# ULA.net
KiCad netlist of a schematic drawn in EAGLE
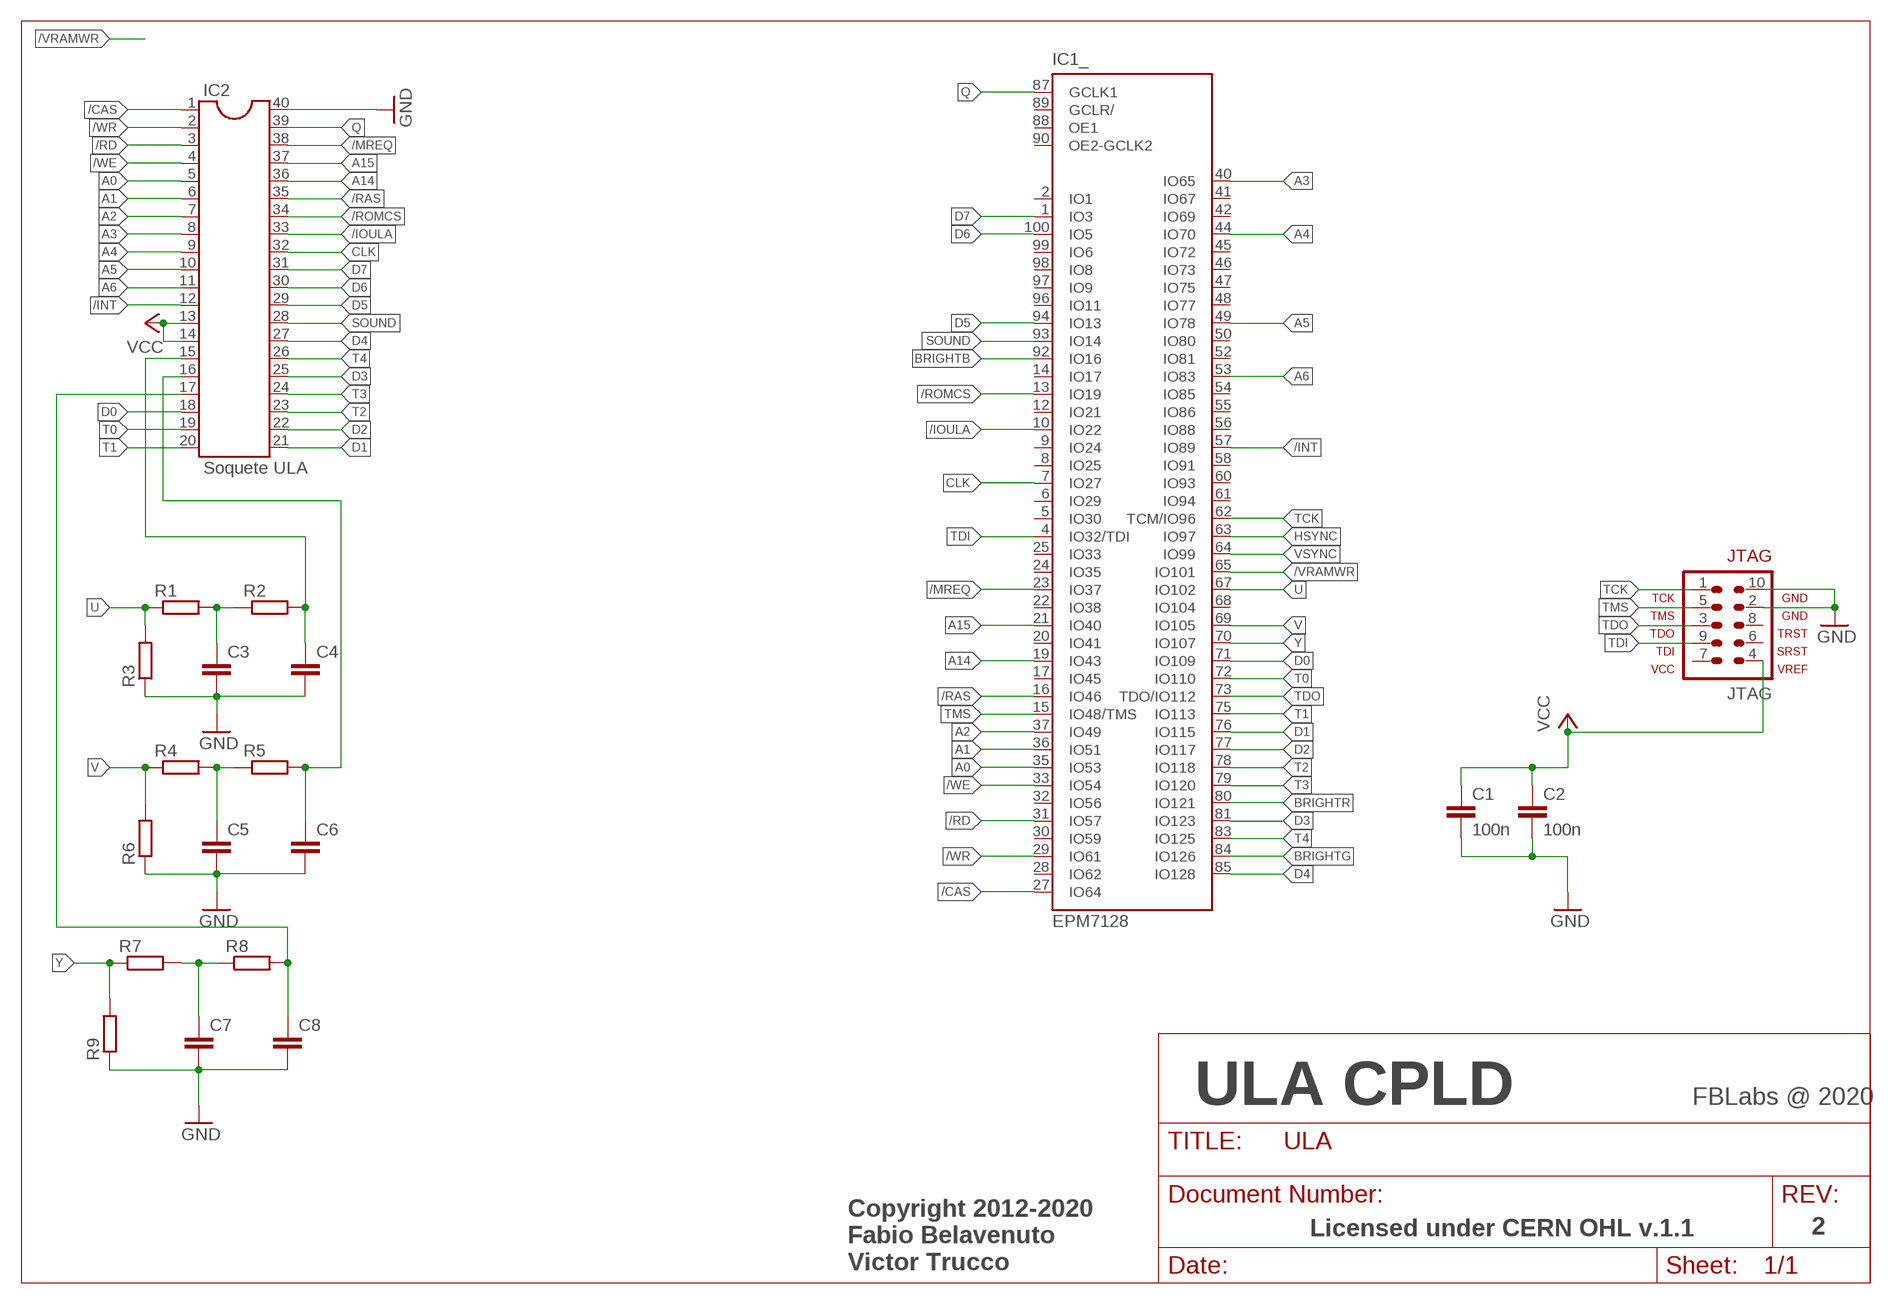
[diagram p0: schematic, sheet 1]

(export (version "E")
  (design (tool "Eeschema 10.0.6"))
  (components
    (comp (ref "C1")
      (value "100n")
      (footprint "eagle-import:C1206")
      (libsource (lib "eagle-import") (part "C-EUC1206"))
    )
    (comp (ref "C2")
      (value "100n")
      (footprint "eagle-import:C1206")
      (libsource (lib "eagle-import") (part "C-EUC1206"))
    )
    (comp (ref "C3")
      (value "C-EUC0805K")
      (footprint "eagle-import:C0805K")
      (libsource (lib "eagle-import") (part "rcl_334_C-EUC0805K"))
    )
    (comp (ref "C4")
      (value "C-EUC0805K")
      (footprint "eagle-import:C0805K")
      (libsource (lib "eagle-import") (part "rcl_334_C-EUC0805K"))
    )
    (comp (ref "C5")
      (value "C-EUC0805K")
      (footprint "eagle-import:C0805K")
      (libsource (lib "eagle-import") (part "rcl_334_C-EUC0805K"))
    )
    (comp (ref "C6")
      (value "C-EUC0805K")
      (footprint "eagle-import:C0805K")
      (libsource (lib "eagle-import") (part "rcl_334_C-EUC0805K"))
    )
    (comp (ref "C7")
      (value "C-EUC0805K")
      (footprint "eagle-import:C0805K")
      (libsource (lib "eagle-import") (part "rcl_334_C-EUC0805K"))
    )
    (comp (ref "C8")
      (value "C-EUC0805K")
      (footprint "eagle-import:C0805K")
      (libsource (lib "eagle-import") (part "rcl_334_C-EUC0805K"))
    )
    (comp (ref "IC1")
      (value "EPM7128")
      (footprint "eagle-import:TQFP100")
      (fields (field (name "MPN") "EPM7128STC100-7N"))
      (libsource (lib "eagle-import") (part "EPM7128-?100T"))
    )
    (comp (ref "IC2")
      (value "Soquete ULA")
      (footprint "eagle-import:DIL40")
      (libsource (lib "eagle-import") (part "DIL40"))
    )
    (comp (ref "JTAG")
      (value "AVR-JTAG-10")
      (footprint "eagle-import:AVR-JTAG-10")
      (libsource (lib "eagle-import") (part "AVR-JTAG-10"))
    )
    (comp (ref "R1")
      (value "R-EU_M0805")
      (footprint "eagle-import:M0805")
      (libsource (lib "eagle-import") (part "R-EU_M0805"))
    )
    (comp (ref "R2")
      (value "R-EU_M0805")
      (footprint "eagle-import:M0805")
      (libsource (lib "eagle-import") (part "R-EU_M0805"))
    )
    (comp (ref "R3")
      (value "R-EU_M0805")
      (footprint "eagle-import:M0805")
      (libsource (lib "eagle-import") (part "R-EU_M0805"))
    )
    (comp (ref "R4")
      (value "R-EU_M0805")
      (footprint "eagle-import:M0805")
      (libsource (lib "eagle-import") (part "R-EU_M0805"))
    )
    (comp (ref "R5")
      (value "R-EU_M0805")
      (footprint "eagle-import:M0805")
      (libsource (lib "eagle-import") (part "R-EU_M0805"))
    )
    (comp (ref "R6")
      (value "R-EU_M0805")
      (footprint "eagle-import:M0805")
      (libsource (lib "eagle-import") (part "R-EU_M0805"))
    )
    (comp (ref "R7")
      (value "R-EU_M0805")
      (footprint "eagle-import:M0805")
      (libsource (lib "eagle-import") (part "R-EU_M0805"))
    )
    (comp (ref "R8")
      (value "R-EU_M0805")
      (footprint "eagle-import:M0805")
      (libsource (lib "eagle-import") (part "R-EU_M0805"))
    )
    (comp (ref "R9")
      (value "R-EU_M0805")
      (footprint "eagle-import:M0805")
      (libsource (lib "eagle-import") (part "R-EU_M0805"))
    )
  )
  (nets
    (net (code "1") (name "A0") (class "Default")
      (node (ref "IC1") (pin "35") (pinfunction "IO53_35") (pintype "bidirectional"))
      (node (ref "IC2") (pin "5") (pinfunction "5_5") (pintype "passive"))
    )
    (net (code "2") (name "A1") (class "Default")
      (node (ref "IC1") (pin "36") (pinfunction "IO51_36") (pintype "bidirectional"))
      (node (ref "IC2") (pin "6") (pinfunction "6_6") (pintype "passive"))
    )
    (net (code "3") (name "A2") (class "Default")
      (node (ref "IC1") (pin "37") (pinfunction "IO49_37") (pintype "bidirectional"))
      (node (ref "IC2") (pin "7") (pinfunction "7_7") (pintype "passive"))
    )
    (net (code "4") (name "A3") (class "Default")
      (node (ref "IC1") (pin "40") (pinfunction "IO65_40") (pintype "bidirectional"))
      (node (ref "IC2") (pin "8") (pinfunction "8_8") (pintype "passive"))
    )
    (net (code "5") (name "A4") (class "Default")
      (node (ref "IC1") (pin "44") (pinfunction "IO70_44") (pintype "bidirectional"))
      (node (ref "IC2") (pin "9") (pinfunction "9_9") (pintype "passive"))
    )
    (net (code "6") (name "A5") (class "Default")
      (node (ref "IC1") (pin "49") (pinfunction "IO78_49") (pintype "bidirectional"))
      (node (ref "IC2") (pin "10") (pinfunction "10_10") (pintype "passive"))
    )
    (net (code "7") (name "A6") (class "Default")
      (node (ref "IC1") (pin "53") (pinfunction "IO83_53") (pintype "bidirectional"))
      (node (ref "IC2") (pin "11") (pinfunction "11_11") (pintype "passive"))
    )
    (net (code "8") (name "A14") (class "Default")
      (node (ref "IC1") (pin "19") (pinfunction "IO43_19") (pintype "bidirectional"))
      (node (ref "IC2") (pin "36") (pinfunction "36_36") (pintype "passive"))
    )
    (net (code "9") (name "A15") (class "Default")
      (node (ref "IC1") (pin "21") (pinfunction "IO40_21") (pintype "bidirectional"))
      (node (ref "IC2") (pin "37") (pinfunction "37_37") (pintype "passive"))
    )
    (net (code "10") (name "BRIGHTB") (class "Default")
      (node (ref "IC1") (pin "92") (pinfunction "IO16_92") (pintype "bidirectional"))
    )
    (net (code "11") (name "BRIGHTG") (class "Default")
      (node (ref "IC1") (pin "84") (pinfunction "IO126_84") (pintype "bidirectional"))
    )
    (net (code "12") (name "BRIGHTR") (class "Default")
      (node (ref "IC1") (pin "80") (pinfunction "IO121_80") (pintype "bidirectional"))
    )
    (net (code "13") (name "CLK") (class "Default")
      (node (ref "IC1") (pin "7") (pinfunction "IO27_7") (pintype "bidirectional"))
      (node (ref "IC2") (pin "32") (pinfunction "32_32") (pintype "passive"))
    )
    (net (code "14") (name "D0") (class "Default")
      (node (ref "IC1") (pin "71") (pinfunction "IO109_71") (pintype "bidirectional"))
      (node (ref "IC2") (pin "18") (pinfunction "18_18") (pintype "passive"))
    )
    (net (code "15") (name "D1") (class "Default")
      (node (ref "IC1") (pin "76") (pinfunction "IO115_76") (pintype "bidirectional"))
      (node (ref "IC2") (pin "21") (pinfunction "21_21") (pintype "passive"))
    )
    (net (code "16") (name "D2") (class "Default")
      (node (ref "IC1") (pin "77") (pinfunction "IO117_77") (pintype "bidirectional"))
      (node (ref "IC2") (pin "22") (pinfunction "22_22") (pintype "passive"))
    )
    (net (code "17") (name "D3") (class "Default")
      (node (ref "IC1") (pin "81") (pinfunction "IO123_81") (pintype "bidirectional"))
      (node (ref "IC2") (pin "25") (pinfunction "25_25") (pintype "passive"))
    )
    (net (code "18") (name "D4") (class "Default")
      (node (ref "IC1") (pin "85") (pinfunction "IO128_85") (pintype "bidirectional"))
      (node (ref "IC2") (pin "27") (pinfunction "27_27") (pintype "passive"))
    )
    (net (code "19") (name "D5") (class "Default")
      (node (ref "IC1") (pin "94") (pinfunction "IO13_94") (pintype "bidirectional"))
      (node (ref "IC2") (pin "29") (pinfunction "29_29") (pintype "passive"))
    )
    (net (code "20") (name "D6") (class "Default")
      (node (ref "IC1") (pin "100") (pinfunction "IO5_100") (pintype "bidirectional"))
      (node (ref "IC2") (pin "30") (pinfunction "30_30") (pintype "passive"))
    )
    (net (code "21") (name "D7") (class "Default")
      (node (ref "IC1") (pin "1") (pinfunction "IO3_1") (pintype "bidirectional"))
      (node (ref "IC2") (pin "31") (pinfunction "31_31") (pintype "passive"))
    )
    (net (code "22") (name "GND") (class "Default")
      (node (ref "C1") (pin "2") (pinfunction "2_2") (pintype "passive"))
      (node (ref "C2") (pin "2") (pinfunction "2_2") (pintype "passive"))
      (node (ref "C3") (pin "2") (pinfunction "2_2") (pintype "passive"))
      (node (ref "C4") (pin "2") (pinfunction "2_2") (pintype "passive"))
      (node (ref "C5") (pin "2") (pinfunction "2_2") (pintype "passive"))
      (node (ref "C6") (pin "2") (pinfunction "2_2") (pintype "passive"))
      (node (ref "C7") (pin "2") (pinfunction "2_2") (pintype "passive"))
      (node (ref "C8") (pin "2") (pinfunction "2_2") (pintype "passive"))
      (node (ref "IC2") (pin "40") (pinfunction "40_40") (pintype "passive"))
      (node (ref "JTAG") (pin "10") (pinfunction "10_10") (pintype "passive"))
      (node (ref "JTAG") (pin "2") (pinfunction "2_2") (pintype "passive"))
      (node (ref "R3") (pin "1") (pinfunction "1_1") (pintype "passive"))
      (node (ref "R6") (pin "1") (pinfunction "1_1") (pintype "passive"))
      (node (ref "R9") (pin "1") (pinfunction "1_1") (pintype "passive"))
    )
    (net (code "23") (name "HSYNC") (class "Default")
      (node (ref "IC1") (pin "63") (pinfunction "IO97_63") (pintype "bidirectional"))
    )
    (net (code "24") (name "Net-(C3-Pad1)") (class "Default")
      (node (ref "C3") (pin "1") (pinfunction "1_1") (pintype "passive"))
      (node (ref "R1") (pin "2") (pinfunction "2_2") (pintype "passive"))
      (node (ref "R2") (pin "1") (pinfunction "1_1") (pintype "passive"))
    )
    (net (code "25") (name "Net-(C4-Pad1)") (class "Default")
      (node (ref "C4") (pin "1") (pinfunction "1_1") (pintype "passive"))
      (node (ref "IC2") (pin "15") (pinfunction "15_15") (pintype "passive"))
      (node (ref "R2") (pin "2") (pinfunction "2_2") (pintype "passive"))
    )
    (net (code "26") (name "Net-(C5-Pad1)") (class "Default")
      (node (ref "C5") (pin "1") (pinfunction "1_1") (pintype "passive"))
      (node (ref "R4") (pin "2") (pinfunction "2_2") (pintype "passive"))
      (node (ref "R5") (pin "1") (pinfunction "1_1") (pintype "passive"))
    )
    (net (code "27") (name "Net-(C6-Pad1)") (class "Default")
      (node (ref "C6") (pin "1") (pinfunction "1_1") (pintype "passive"))
      (node (ref "IC2") (pin "16") (pinfunction "16_16") (pintype "passive"))
      (node (ref "R5") (pin "2") (pinfunction "2_2") (pintype "passive"))
    )
    (net (code "28") (name "Net-(C7-Pad1)") (class "Default")
      (node (ref "C7") (pin "1") (pinfunction "1_1") (pintype "passive"))
      (node (ref "R7") (pin "2") (pinfunction "2_2") (pintype "passive"))
      (node (ref "R8") (pin "1") (pinfunction "1_1") (pintype "passive"))
    )
    (net (code "29") (name "Net-(C8-Pad1)") (class "Default")
      (node (ref "C8") (pin "1") (pinfunction "1_1") (pintype "passive"))
      (node (ref "IC2") (pin "17") (pinfunction "17_17") (pintype "passive"))
      (node (ref "R8") (pin "2") (pinfunction "2_2") (pintype "passive"))
    )
    (net (code "30") (name "Q") (class "Default")
      (node (ref "IC1") (pin "87") (pinfunction "GCLK1_87") (pintype "input"))
      (node (ref "IC2") (pin "39") (pinfunction "39_39") (pintype "passive"))
    )
    (net (code "31") (name "SOUND") (class "Default")
      (node (ref "IC1") (pin "93") (pinfunction "IO14_93") (pintype "bidirectional"))
      (node (ref "IC2") (pin "28") (pinfunction "28_28") (pintype "passive"))
    )
    (net (code "32") (name "T0") (class "Default")
      (node (ref "IC1") (pin "72") (pinfunction "IO110_72") (pintype "bidirectional"))
      (node (ref "IC2") (pin "19") (pinfunction "19_19") (pintype "passive"))
    )
    (net (code "33") (name "T1") (class "Default")
      (node (ref "IC1") (pin "75") (pinfunction "IO113_75") (pintype "bidirectional"))
      (node (ref "IC2") (pin "20") (pinfunction "20_20") (pintype "passive"))
    )
    (net (code "34") (name "T2") (class "Default")
      (node (ref "IC1") (pin "78") (pinfunction "IO118_78") (pintype "bidirectional"))
      (node (ref "IC2") (pin "23") (pinfunction "23_23") (pintype "passive"))
    )
    (net (code "35") (name "T3") (class "Default")
      (node (ref "IC1") (pin "79") (pinfunction "IO120_79") (pintype "bidirectional"))
      (node (ref "IC2") (pin "24") (pinfunction "24_24") (pintype "passive"))
    )
    (net (code "36") (name "T4") (class "Default")
      (node (ref "IC1") (pin "83") (pinfunction "IO125_83") (pintype "bidirectional"))
      (node (ref "IC2") (pin "26") (pinfunction "26_26") (pintype "passive"))
    )
    (net (code "37") (name "TCK") (class "Default")
      (node (ref "IC1") (pin "62") (pinfunction "TCM/IO96_62") (pintype "bidirectional"))
      (node (ref "JTAG") (pin "1") (pinfunction "1_1") (pintype "passive"))
    )
    (net (code "38") (name "TDI") (class "Default")
      (node (ref "IC1") (pin "4") (pinfunction "IO32/TDI_4") (pintype "bidirectional"))
      (node (ref "JTAG") (pin "9") (pinfunction "9_9") (pintype "passive"))
    )
    (net (code "39") (name "TDO") (class "Default")
      (node (ref "IC1") (pin "73") (pinfunction "TDO/IO112_73") (pintype "bidirectional"))
      (node (ref "JTAG") (pin "3") (pinfunction "3_3") (pintype "passive"))
    )
    (net (code "40") (name "TMS") (class "Default")
      (node (ref "IC1") (pin "15") (pinfunction "IO48/TMS_15") (pintype "bidirectional"))
      (node (ref "JTAG") (pin "5") (pinfunction "5_5") (pintype "passive"))
    )
    (net (code "41") (name "U") (class "Default")
      (node (ref "IC1") (pin "67") (pinfunction "IO102_67") (pintype "bidirectional"))
      (node (ref "R1") (pin "1") (pinfunction "1_1") (pintype "passive"))
      (node (ref "R3") (pin "2") (pinfunction "2_2") (pintype "passive"))
    )
    (net (code "42") (name "V") (class "Default")
      (node (ref "IC1") (pin "69") (pinfunction "IO105_69") (pintype "bidirectional"))
      (node (ref "R4") (pin "1") (pinfunction "1_1") (pintype "passive"))
      (node (ref "R6") (pin "2") (pinfunction "2_2") (pintype "passive"))
    )
    (net (code "43") (name "VCC") (class "Default")
      (node (ref "C1") (pin "1") (pinfunction "1_1") (pintype "passive"))
      (node (ref "C2") (pin "1") (pinfunction "1_1") (pintype "passive"))
      (node (ref "IC2") (pin "13") (pinfunction "13_13") (pintype "passive"))
      (node (ref "IC2") (pin "14") (pinfunction "14_14") (pintype "passive"))
      (node (ref "JTAG") (pin "4") (pinfunction "4_4") (pintype "passive"))
    )
    (net (code "44") (name "VSYNC") (class "Default")
      (node (ref "IC1") (pin "64") (pinfunction "IO99_64") (pintype "bidirectional"))
    )
    (net (code "45") (name "Y") (class "Default")
      (node (ref "IC1") (pin "70") (pinfunction "IO107_70") (pintype "bidirectional"))
      (node (ref "R7") (pin "1") (pinfunction "1_1") (pintype "passive"))
      (node (ref "R9") (pin "2") (pinfunction "2_2") (pintype "passive"))
    )
    (net (code "46") (name "unconnected-(IC1Q-GCLR{slash}-Pad89)") (class "Default")
      (node (ref "IC1") (pin "89") (pinfunction "GCLR/_89") (pintype "input"))
    )
    (net (code "47") (name "unconnected-(IC1Q-IO1-Pad2)") (class "Default")
      (node (ref "IC1") (pin "2") (pinfunction "IO1_2") (pintype "bidirectional"))
    )
    (net (code "48") (name "unconnected-(IC1Q-IO6-Pad99)") (class "Default")
      (node (ref "IC1") (pin "99") (pinfunction "IO6_99") (pintype "bidirectional"))
    )
    (net (code "49") (name "unconnected-(IC1Q-IO8-Pad98)") (class "Default")
      (node (ref "IC1") (pin "98") (pinfunction "IO8_98") (pintype "bidirectional"))
    )
    (net (code "50") (name "unconnected-(IC1Q-IO9-Pad97)") (class "Default")
      (node (ref "IC1") (pin "97") (pinfunction "IO9_97") (pintype "bidirectional"))
    )
    (net (code "51") (name "unconnected-(IC1Q-IO11-Pad96)") (class "Default")
      (node (ref "IC1") (pin "96") (pinfunction "IO11_96") (pintype "bidirectional"))
    )
    (net (code "52") (name "unconnected-(IC1Q-IO17-Pad14)") (class "Default")
      (node (ref "IC1") (pin "14") (pinfunction "IO17_14") (pintype "bidirectional"))
    )
    (net (code "53") (name "unconnected-(IC1Q-IO21-Pad12)") (class "Default")
      (node (ref "IC1") (pin "12") (pinfunction "IO21_12") (pintype "bidirectional"))
    )
    (net (code "54") (name "unconnected-(IC1Q-IO24-Pad9)") (class "Default")
      (node (ref "IC1") (pin "9") (pinfunction "IO24_9") (pintype "bidirectional"))
    )
    (net (code "55") (name "unconnected-(IC1Q-IO25-Pad8)") (class "Default")
      (node (ref "IC1") (pin "8") (pinfunction "IO25_8") (pintype "bidirectional"))
    )
    (net (code "56") (name "unconnected-(IC1Q-IO29-Pad6)") (class "Default")
      (node (ref "IC1") (pin "6") (pinfunction "IO29_6") (pintype "bidirectional"))
    )
    (net (code "57") (name "unconnected-(IC1Q-IO30-Pad5)") (class "Default")
      (node (ref "IC1") (pin "5") (pinfunction "IO30_5") (pintype "bidirectional"))
    )
    (net (code "58") (name "unconnected-(IC1Q-IO33-Pad25)") (class "Default")
      (node (ref "IC1") (pin "25") (pinfunction "IO33_25") (pintype "bidirectional"))
    )
    (net (code "59") (name "unconnected-(IC1Q-IO35-Pad24)") (class "Default")
      (node (ref "IC1") (pin "24") (pinfunction "IO35_24") (pintype "bidirectional"))
    )
    (net (code "60") (name "unconnected-(IC1Q-IO38-Pad22)") (class "Default")
      (node (ref "IC1") (pin "22") (pinfunction "IO38_22") (pintype "bidirectional"))
    )
    (net (code "61") (name "unconnected-(IC1Q-IO41-Pad20)") (class "Default")
      (node (ref "IC1") (pin "20") (pinfunction "IO41_20") (pintype "bidirectional"))
    )
    (net (code "62") (name "unconnected-(IC1Q-IO45-Pad17)") (class "Default")
      (node (ref "IC1") (pin "17") (pinfunction "IO45_17") (pintype "bidirectional"))
    )
    (net (code "63") (name "unconnected-(IC1Q-IO56-Pad32)") (class "Default")
      (node (ref "IC1") (pin "32") (pinfunction "IO56_32") (pintype "bidirectional"))
    )
    (net (code "64") (name "unconnected-(IC1Q-IO59-Pad30)") (class "Default")
      (node (ref "IC1") (pin "30") (pinfunction "IO59_30") (pintype "bidirectional"))
    )
    (net (code "65") (name "unconnected-(IC1Q-IO62-Pad28)") (class "Default")
      (node (ref "IC1") (pin "28") (pinfunction "IO62_28") (pintype "bidirectional"))
    )
    (net (code "66") (name "unconnected-(IC1Q-IO67-Pad41)") (class "Default")
      (node (ref "IC1") (pin "41") (pinfunction "IO67_41") (pintype "bidirectional"))
    )
    (net (code "67") (name "unconnected-(IC1Q-IO69-Pad42)") (class "Default")
      (node (ref "IC1") (pin "42") (pinfunction "IO69_42") (pintype "bidirectional"))
    )
    (net (code "68") (name "unconnected-(IC1Q-IO72-Pad45)") (class "Default")
      (node (ref "IC1") (pin "45") (pinfunction "IO72_45") (pintype "bidirectional"))
    )
    (net (code "69") (name "unconnected-(IC1Q-IO73-Pad46)") (class "Default")
      (node (ref "IC1") (pin "46") (pinfunction "IO73_46") (pintype "bidirectional"))
    )
    (net (code "70") (name "unconnected-(IC1Q-IO75-Pad47)") (class "Default")
      (node (ref "IC1") (pin "47") (pinfunction "IO75_47") (pintype "bidirectional"))
    )
    (net (code "71") (name "unconnected-(IC1Q-IO77-Pad48)") (class "Default")
      (node (ref "IC1") (pin "48") (pinfunction "IO77_48") (pintype "bidirectional"))
    )
    (net (code "72") (name "unconnected-(IC1Q-IO80-Pad50)") (class "Default")
      (node (ref "IC1") (pin "50") (pinfunction "IO80_50") (pintype "bidirectional"))
    )
    (net (code "73") (name "unconnected-(IC1Q-IO81-Pad52)") (class "Default")
      (node (ref "IC1") (pin "52") (pinfunction "IO81_52") (pintype "bidirectional"))
    )
    (net (code "74") (name "unconnected-(IC1Q-IO85-Pad54)") (class "Default")
      (node (ref "IC1") (pin "54") (pinfunction "IO85_54") (pintype "bidirectional"))
    )
    (net (code "75") (name "unconnected-(IC1Q-IO86-Pad55)") (class "Default")
      (node (ref "IC1") (pin "55") (pinfunction "IO86_55") (pintype "bidirectional"))
    )
    (net (code "76") (name "unconnected-(IC1Q-IO88-Pad56)") (class "Default")
      (node (ref "IC1") (pin "56") (pinfunction "IO88_56") (pintype "bidirectional"))
    )
    (net (code "77") (name "unconnected-(IC1Q-IO91-Pad58)") (class "Default")
      (node (ref "IC1") (pin "58") (pinfunction "IO91_58") (pintype "bidirectional"))
    )
    (net (code "78") (name "unconnected-(IC1Q-IO93-Pad60)") (class "Default")
      (node (ref "IC1") (pin "60") (pinfunction "IO93_60") (pintype "bidirectional"))
    )
    (net (code "79") (name "unconnected-(IC1Q-IO94-Pad61)") (class "Default")
      (node (ref "IC1") (pin "61") (pinfunction "IO94_61") (pintype "bidirectional"))
    )
    (net (code "80") (name "unconnected-(IC1Q-IO104-Pad68)") (class "Default")
      (node (ref "IC1") (pin "68") (pinfunction "IO104_68") (pintype "bidirectional"))
    )
    (net (code "81") (name "unconnected-(IC1Q-OE1-Pad88)") (class "Default")
      (node (ref "IC1") (pin "88") (pinfunction "OE1_88") (pintype "input"))
    )
    (net (code "82") (name "unconnected-(IC1Q-OE2-GCLK2-Pad90)") (class "Default")
      (node (ref "IC1") (pin "90") (pinfunction "OE2-GCLK2_90") (pintype "input"))
    )
    (net (code "83") (name "unconnected-(JTAG-Pad6)") (class "Default")
      (node (ref "JTAG") (pin "6") (pinfunction "6_6") (pintype "passive"))
    )
    (net (code "84") (name "unconnected-(JTAG-Pad7)") (class "Default")
      (node (ref "JTAG") (pin "7") (pinfunction "7_7") (pintype "passive"))
    )
    (net (code "85") (name "unconnected-(JTAG-Pad8)") (class "Default")
      (node (ref "JTAG") (pin "8") (pinfunction "8_8") (pintype "passive"))
    )
    (net (code "86") (name "{slash}CAS") (class "Default")
      (node (ref "IC1") (pin "27") (pinfunction "IO64_27") (pintype "bidirectional"))
      (node (ref "IC2") (pin "1") (pinfunction "1_1") (pintype "passive"))
    )
    (net (code "87") (name "{slash}INT") (class "Default")
      (node (ref "IC1") (pin "57") (pinfunction "IO89_57") (pintype "bidirectional"))
      (node (ref "IC2") (pin "12") (pinfunction "12_12") (pintype "passive"))
    )
    (net (code "88") (name "{slash}IOULA") (class "Default")
      (node (ref "IC1") (pin "10") (pinfunction "IO22_10") (pintype "bidirectional"))
      (node (ref "IC2") (pin "33") (pinfunction "33_33") (pintype "passive"))
    )
    (net (code "89") (name "{slash}MREQ") (class "Default")
      (node (ref "IC1") (pin "23") (pinfunction "IO37_23") (pintype "bidirectional"))
      (node (ref "IC2") (pin "38") (pinfunction "38_38") (pintype "passive"))
    )
    (net (code "90") (name "{slash}RAS") (class "Default")
      (node (ref "IC1") (pin "16") (pinfunction "IO46_16") (pintype "bidirectional"))
      (node (ref "IC2") (pin "35") (pinfunction "35_35") (pintype "passive"))
    )
    (net (code "91") (name "{slash}RD") (class "Default")
      (node (ref "IC1") (pin "31") (pinfunction "IO57_31") (pintype "bidirectional"))
      (node (ref "IC2") (pin "3") (pinfunction "3_3") (pintype "passive"))
    )
    (net (code "92") (name "{slash}ROMCS") (class "Default")
      (node (ref "IC1") (pin "13") (pinfunction "IO19_13") (pintype "bidirectional"))
      (node (ref "IC2") (pin "34") (pinfunction "34_34") (pintype "passive"))
    )
    (net (code "93") (name "{slash}VRAMWR") (class "Default")
      (node (ref "IC1") (pin "65") (pinfunction "IO101_65") (pintype "bidirectional"))
    )
    (net (code "94") (name "{slash}WE") (class "Default")
      (node (ref "IC1") (pin "33") (pinfunction "IO54_33") (pintype "bidirectional"))
      (node (ref "IC2") (pin "4") (pinfunction "4_4") (pintype "passive"))
    )
    (net (code "95") (name "{slash}WR") (class "Default")
      (node (ref "IC1") (pin "29") (pinfunction "IO61_29") (pintype "bidirectional"))
      (node (ref "IC2") (pin "2") (pinfunction "2_2") (pintype "passive"))
    )
  )
)
